# ECGCircuit.net
KiCad netlist of a schematic drawn in Altium Designer
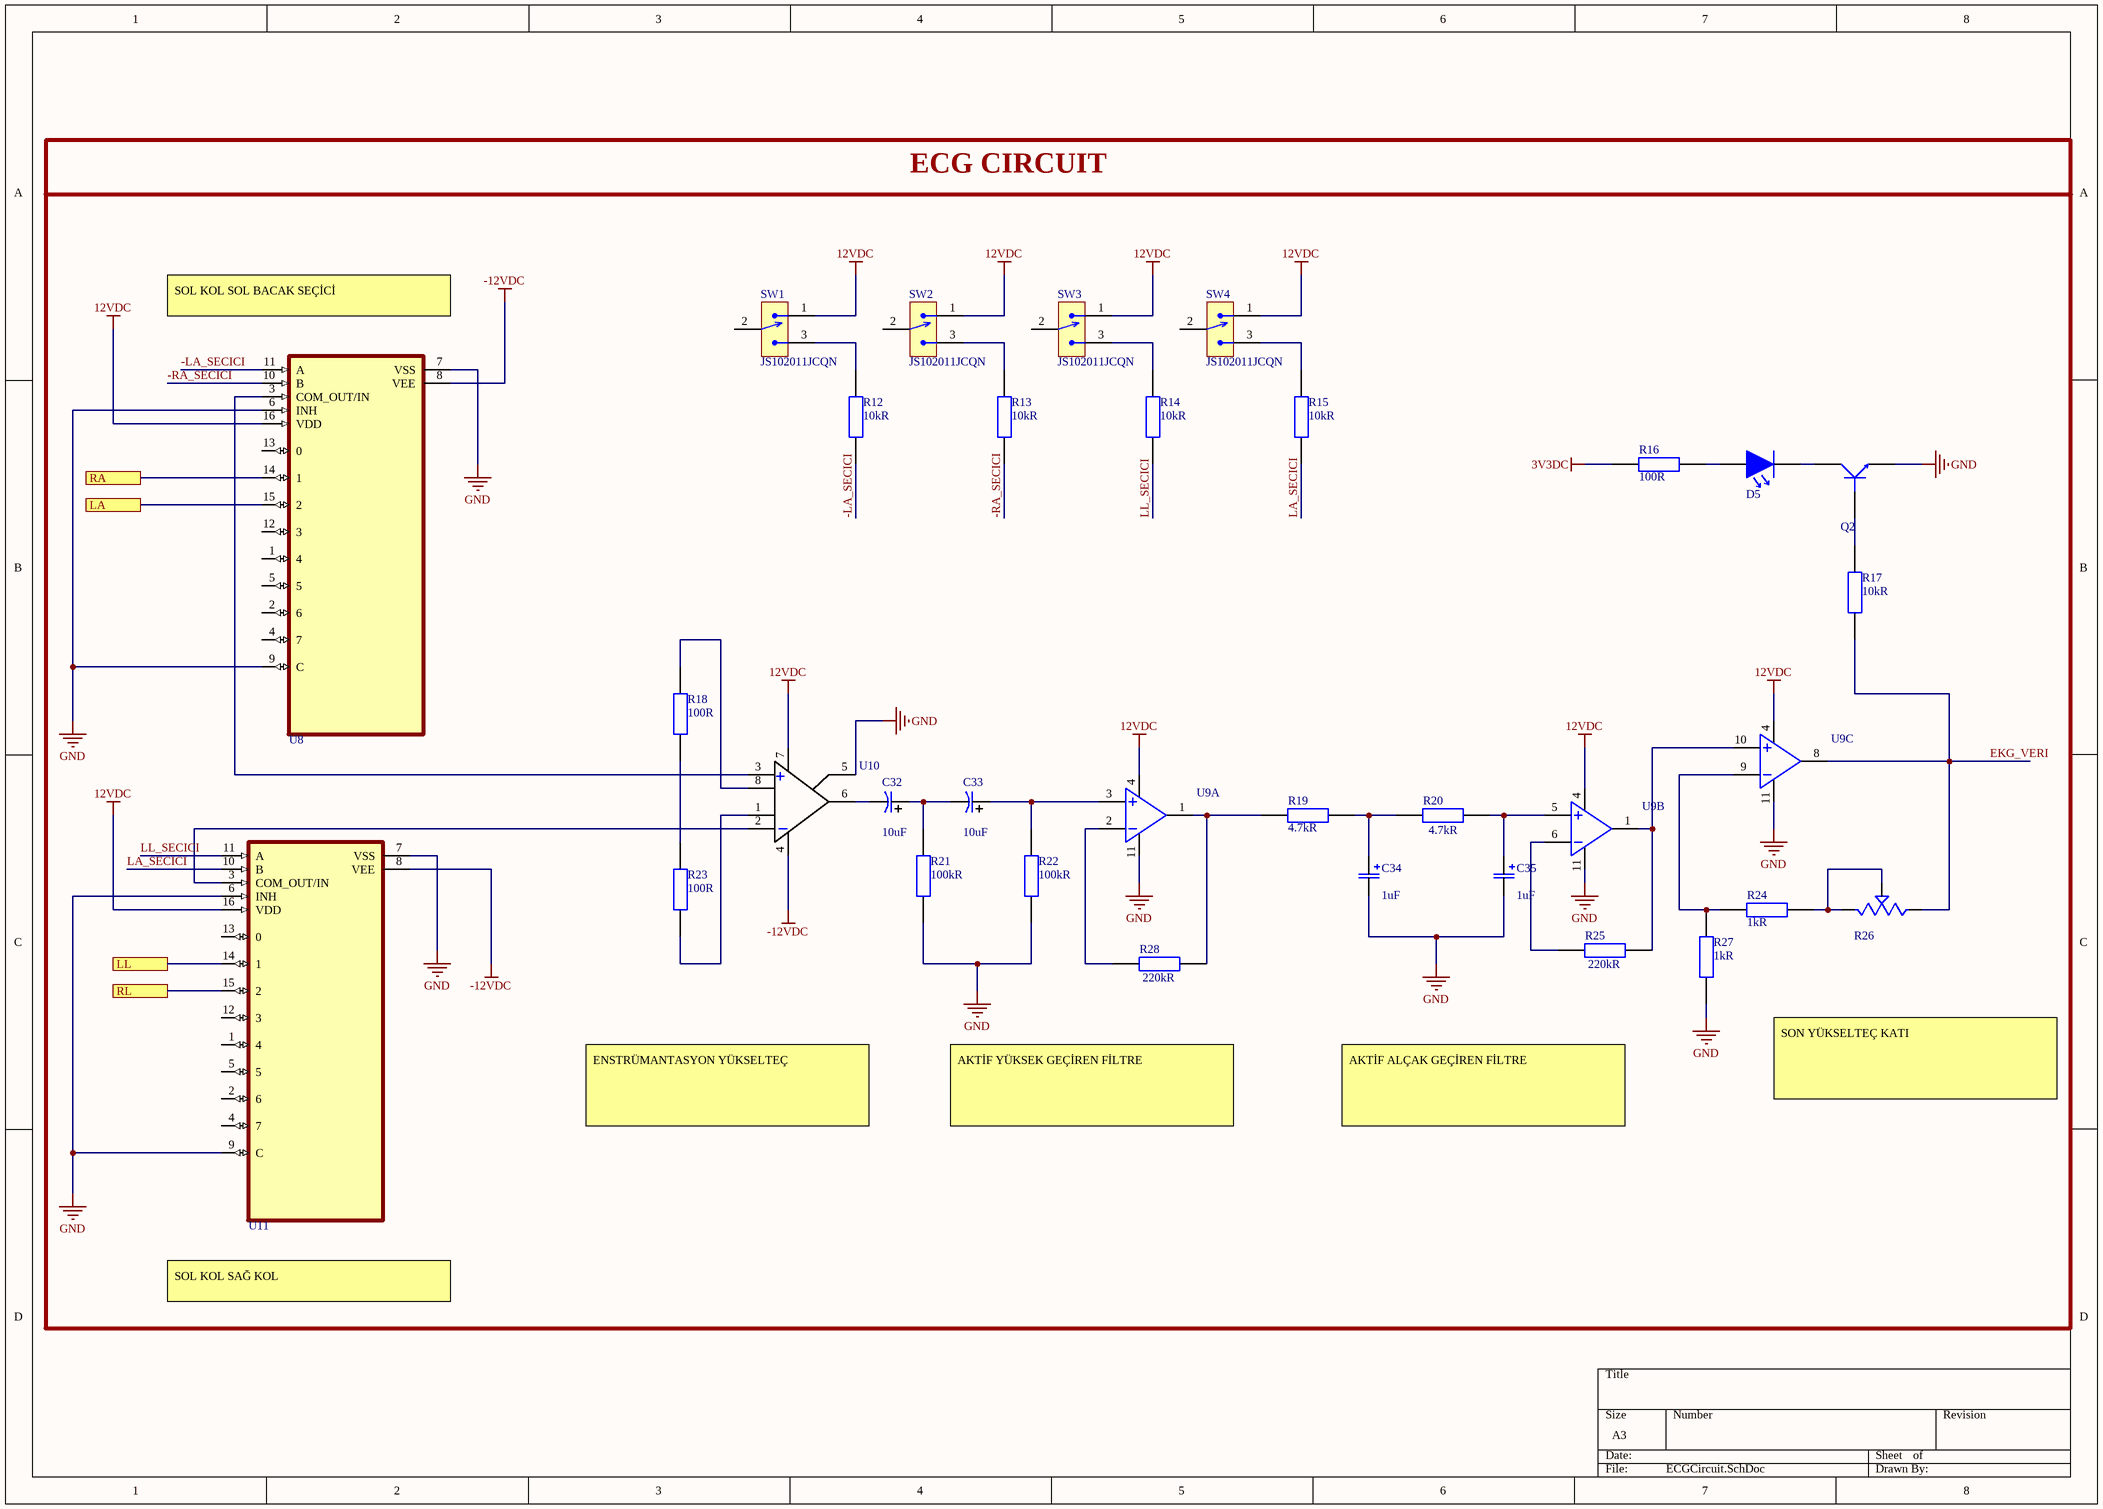
[diagram p0: ECGCircuit.SchDoc]

(export (version "E")
  (design (tool "Eeschema 10.0.6"))
  (components
    (comp (ref "C32")
      (value "AP ALU 10uF")
      (footprint "A700V_KEM")
      (description "CAP ALUM POLY 10UF 20% 12.5V SMD")
      (fields
        (field (name "MANUFACTURER") "KEMET")
        (field (name "MANUFACTURER PART NUMBER") "A700V106M12RATE040")
        (field (name "CAPACITANCE") "10uF")
      )
      (libsource (lib "Udemy_Library") (part "CAP ALU 10uF"))
    )
    (comp (ref "C33")
      (value "ALU 10uF")
      (footprint "A700V_KEM")
      (description "CAP ALUM POLY 10UF 20% 12.5V SMD")
      (fields
        (field (name "MANUFACTURER") "KEMET")
        (field (name "MANUFACTURER PART NUMBER") "A700V106M12RATE040")
        (field (name "CAPACITANCE") "10uF")
      )
      (libsource (lib "Udemy_Library") (part "CAP ALU 10uF"))
    )
    (comp (ref "C34")
      (value "CAP ALU 1uF")
      (footprint "EXV-9B_KEM")
      (description "KEMET - EXV105M050A9BAA - CAP, 1µF, 50V, RADIAL, SMD")
      (fields
        (field (name "MANUFACTURER") "KEMET")
        (field (name "MANUFACTURER PART NUMBER") "EXV105M050A9BAA")
        (field (name "CAPACITANCE") "1uF")
      )
      (libsource (lib "Udemy_Library") (part "CAP ALU 1uF"))
    )
    (comp (ref "C35")
      (value "CAP ALU 1uF")
      (footprint "EXV-9B_KEM")
      (description "KEMET - EXV105M050A9BAA - CAP, 1µF, 50V, RADIAL, SMD")
      (fields
        (field (name "MANUFACTURER") "KEMET")
        (field (name "MANUFACTURER PART NUMBER") "EXV105M050A9BAA")
        (field (name "CAPACITANCE") "1uF")
      )
      (libsource (lib "Udemy_Library") (part "CAP ALU 1uF"))
    )
    (comp (ref "D5")
      (value "LH R974-LP-1")
      (footprint "LED_RED_0805")
      (description "LED Uni-Color Hyper Red 660nm 2-Pin Chip 0805(2012Metric) T/R")
      (fields (field (name "MANUFACTURER") "Osram Opto") (field (name "DESIGNED BY") "TALAT"))
      (libsource (lib "Udemy_Library") (part "LED RED 0805"))
    )
    (comp (ref "Q2")
      (value "MMBT3904-7-F")
      (footprint "SOT-23F")
      (description "Transistor General Purpose BJT NPN 40 Volt 0.2A Automotive 3-Pin SOT-23")
      (fields (field (name "MANUFACTURER") "Diodes Zetex") (field (name "DESIGNED BY") "TALAT"))
      (libsource (lib "Udemy_Library") (part "MMBT3904-7-F"))
    )
    (comp (ref "R12")
      (value "RC0603FR-0710KL")
      (footprint "RES_0603")
      (description "RES 10K %1 OHM 0603 SMD")
      (fields
        (field (name "MANUFACTURER") "Yageo")
        (field (name "TOLERANCE") "1%")
        (field (name "RESISTANCE") "10kR")
        (field (name "DESIGNED BY") "TALAT")
      )
      (libsource (lib "Udemy_Library") (part "RES 10K OHM 0603"))
    )
    (comp (ref "R13")
      (value "RC0603FR-0710KL")
      (footprint "RES_0603")
      (description "RES 10K %1 OHM 0603 SMD")
      (fields
        (field (name "MANUFACTURER") "Yageo")
        (field (name "TOLERANCE") "1%")
        (field (name "RESISTANCE") "10kR")
        (field (name "DESIGNED BY") "TALAT")
      )
      (libsource (lib "Udemy_Library") (part "RES 10K OHM 0603"))
    )
    (comp (ref "R14")
      (value "RC0603FR-0710KL")
      (footprint "RES_0603")
      (description "RES 10K %1 OHM 0603 SMD")
      (fields
        (field (name "MANUFACTURER") "Yageo")
        (field (name "TOLERANCE") "1%")
        (field (name "RESISTANCE") "10kR")
        (field (name "DESIGNED BY") "TALAT")
      )
      (libsource (lib "Udemy_Library") (part "RES 10K OHM 0603"))
    )
    (comp (ref "R15")
      (value "RC0603FR-0710KL")
      (footprint "RES_0603")
      (description "RES 10K %1 OHM 0603 SMD")
      (fields
        (field (name "MANUFACTURER") "Yageo")
        (field (name "TOLERANCE") "1%")
        (field (name "RESISTANCE") "10kR")
        (field (name "DESIGNED BY") "TALAT")
      )
      (libsource (lib "Udemy_Library") (part "RES 10K OHM 0603"))
    )
    (comp (ref "R16")
      (value "RC0603JR-07100RL")
      (footprint "RES_0603")
      (description "RES 100 %5 OHM 0603 SMD")
      (fields
        (field (name "MANUFACTURER") "Yageo")
        (field (name "TOLERANCE") "5%")
        (field (name "RESISTANCE") "100R")
        (field (name "DESIGNED BY") "TALAT")
      )
      (libsource (lib "Udemy_Library") (part "RES 100 OHM 0603"))
    )
    (comp (ref "R17")
      (value "RC0603FR-0710KL")
      (footprint "RES_0603")
      (description "RES 10K %1 OHM 0603 SMD")
      (fields
        (field (name "MANUFACTURER") "Yageo")
        (field (name "TOLERANCE") "1%")
        (field (name "RESISTANCE") "10kR")
        (field (name "DESIGNED BY") "TALAT")
      )
      (libsource (lib "Udemy_Library") (part "RES 10K OHM 0603"))
    )
    (comp (ref "R18")
      (value "RC0603JR-07100RL")
      (footprint "RES_0603")
      (description "RES 100 %5 OHM 0603 SMD")
      (fields
        (field (name "MANUFACTURER") "Yageo")
        (field (name "TOLERANCE") "5%")
        (field (name "RESISTANCE") "100R")
        (field (name "DESIGNED BY") "TALAT")
      )
      (libsource (lib "") (part "RES 100 OHM 0603_1"))
    )
    (comp (ref "R19")
      (value "RC0603JR-074K7L")
      (footprint "RES_0603")
      (description "RES 4K7 %5 OHM 0603 SMD")
      (fields
        (field (name "MANUFACTURER") "Yageo")
        (field (name "TOLERANCE") "5%")
        (field (name "RESISTANCE") "4.7kR")
        (field (name "DESIGNED BY") "TALAT")
      )
      (libsource (lib "Udemy_Library") (part "RES 4K7 OHM 0603"))
    )
    (comp (ref "R20")
      (value "RC0603JR-074K7L")
      (footprint "RES_0603")
      (description "RES 4K7 %5 OHM 0603 SMD")
      (fields
        (field (name "MANUFACTURER") "Yageo")
        (field (name "TOLERANCE") "5%")
        (field (name "RESISTANCE") "4.7kR")
        (field (name "DESIGNED BY") "TALAT")
      )
      (libsource (lib "Udemy_Library") (part "RES 4K7 OHM 0603"))
    )
    (comp (ref "R21")
      (value "RES SMD 100KOHM 0.25% 1/10W 0603")
      (footprint "RES_0603")
      (fields
        (field (name "MANUFACTURER") "Yageo")
        (field (name "MANUFACTURER PART NUMBER") "RT0603CRE07100KL")
        (field (name "TOLERANCE") "0.25%")
        (field (name "RESISTANCE") "100kR")
      )
      (libsource (lib "Udemy_Library") (part "RES 100K OHM 0603"))
    )
    (comp (ref "R22")
      (value "RES SMD 100KOHM 0.25% 1/10W 0603")
      (footprint "RES_0603")
      (fields
        (field (name "MANUFACTURER") "Yageo")
        (field (name "MANUFACTURER PART NUMBER") "RT0603CRE07100KL")
        (field (name "TOLERANCE") "0.25%")
        (field (name "RESISTANCE") "100kR")
      )
      (libsource (lib "Udemy_Library") (part "RES 100K OHM 0603"))
    )
    (comp (ref "R23")
      (value "RC0603JR-07100RL")
      (footprint "RES_0603")
      (description "RES 100 %5 OHM 0603 SMD")
      (fields
        (field (name "MANUFACTURER") "Yageo")
        (field (name "TOLERANCE") "5%")
        (field (name "RESISTANCE") "100R")
        (field (name "DESIGNED BY") "TALAT")
      )
      (libsource (lib "") (part "RES 100 OHM 0603_1"))
    )
    (comp (ref "R24")
      (value "RC0603FR-0710KL")
      (footprint "RES_0603")
      (description "RES 1K %1 OHM 0603 SMD")
      (fields
        (field (name "MANUFACTURER") "Yageo")
        (field (name "MANUFACTURER PART NUMBER") "RC0603JR-071KL")
        (field (name "RESISTANCE") "1kR")
        (field (name "DESIGNED BY") "TALAT")
      )
      (libsource (lib "") (part "RES 1K OHM 0603_1"))
    )
    (comp (ref "R25")
      (value "RC0603JR-07220KL")
      (footprint "RES_0603")
      (description "RES 220K %5 OHM 0603 SMD")
      (fields
        (field (name "MANUFACTURER") "Yageo")
        (field (name "TOLERANCE") "5%")
        (field (name "RESISTANCE") "220kR")
      )
      (libsource (lib "Udemy_Library") (part "RES 220K OHM 0603"))
    )
    (comp (ref "R26")
      (value "TRIMMER, 12 TURN 50K")
      (footprint "3266W-1-503LF")
      (fields
        (field (name "MANUFACTURER") "Bourns")
        (field (name "MANUFACTURER PART NUMBER") "3266W-1-503LF")
        (field (name "TOLERANCE") "10%")
        (field (name "DESIGNED BY") "TALAT")
      )
      (libsource (lib "Udemy_Library") (part "Res POT 50K"))
    )
    (comp (ref "R27")
      (value "RC0603FR-0710KL")
      (footprint "RES_0603")
      (description "RES 1K %1 OHM 0603 SMD")
      (fields
        (field (name "MANUFACTURER") "Yageo")
        (field (name "MANUFACTURER PART NUMBER") "RC0603JR-071KL")
        (field (name "RESISTANCE") "1kR")
        (field (name "DESIGNED BY") "TALAT")
      )
      (libsource (lib "Udemy_Library") (part "RES 1K OHM 0603"))
    )
    (comp (ref "R28")
      (value "RC0603JR-07220KL")
      (footprint "RES_0603")
      (description "RES 220K %5 OHM 0603 SMD")
      (fields
        (field (name "MANUFACTURER") "Yageo")
        (field (name "TOLERANCE") "5%")
        (field (name "RESISTANCE") "220kR")
      )
      (libsource (lib "Udemy_Library") (part "RES 220K OHM 0603"))
    )
    (comp (ref "SW1")
      (value "JS102011JCQN")
      (footprint "JS102011JCQN")
      (libsource (lib "Udemy_Library") (part "JS102011JCQN"))
    )
    (comp (ref "SW2")
      (value "JS102011JCQN")
      (footprint "JS102011JCQN")
      (libsource (lib "Udemy_Library") (part "JS102011JCQN"))
    )
    (comp (ref "SW3")
      (value "JS102011JCQN")
      (footprint "JS102011JCQN")
      (libsource (lib "Udemy_Library") (part "JS102011JCQN"))
    )
    (comp (ref "SW4")
      (value "JS102011JCQN")
      (footprint "JS102011JCQN")
      (libsource (lib "Udemy_Library") (part "JS102011JCQN"))
    )
    (comp (ref "U8")
      (value "CD4051BM")
      (footprint "SOİC16")
      (description "Analog Multiplexer Single 8:1 16-Pin SOIC Tube")
      (fields (field (name "MANUFACTURER") "Texas Instruments"))
      (libsource (lib "Udemy_Library") (part "CD4051BM"))
    )
    (comp (ref "U9")
      (value "IC OPAMP GP 1.3MHZ 14DIP")
      (footprint "SOIC14")
      (fields
        (field (name "MANUFACTURER") "STMicroelectronics")
        (field (name "MANUFACTURER PART NUMBER") "LM324N")
        (field (name "DESIGNED BY") "Talat")
      )
      (libsource (lib "Udemy_Library") (part "OPALM324N"))
    )
    (comp (ref "U10")
      (value "AD620BRZ-R7")
      (footprint "SOIC8")
      (description "SP Amp INSTR Amp Single ±18V 8-Pin SOIC N T/R")
      (fields (field (name "MANUFACTURER") "Analog Devices"))
      (libsource (lib "Udemy_Library") (part "AD620"))
    )
    (comp (ref "U11")
      (value "CD4051BM")
      (footprint "SOİC16")
      (description "Analog Multiplexer Single 8:1 16-Pin SOIC Tube")
      (fields (field (name "MANUFACTURER") "Texas Instruments"))
      (libsource (lib "Udemy_Library") (part "CD4051BM"))
    )
  )
  (nets
    (net (code "1") (name "-12VDC") (class "Default")
      (node (ref "U10") (pin "4") (pinfunction "4_4") (pintype "passive"))
      (node (ref "U11") (pin "8") (pinfunction "VEE_8") (pintype "power_in"))
      (node (ref "U8") (pin "8") (pinfunction "VEE_8") (pintype "power_in"))
    )
    (net (code "2") (name "/-LA_SECICI") (class "Default")
      (node (ref "R12") (pin "1") (pinfunction "1_1") (pintype "passive"))
      (node (ref "U8") (pin "11") (pinfunction "A_11") (pintype "input"))
    )
    (net (code "3") (name "/-RA_SECICI") (class "Default")
      (node (ref "R13") (pin "1") (pinfunction "1_1") (pintype "passive"))
      (node (ref "U8") (pin "10") (pinfunction "B_10") (pintype "input"))
    )
    (net (code "4") (name "/EKG_VERI") (class "Default")
      (node (ref "R17") (pin "1") (pinfunction "1_1") (pintype "passive"))
      (node (ref "R26") (pin "1") (pinfunction "CCW_1") (pintype "passive"))
      (node (ref "U9") (pin "8") (pinfunction "8_8") (pintype "passive"))
    )
    (net (code "5") (name "/LA") (class "Default")
      (node (ref "U8") (pin "15") (pinfunction "2_15") (pintype "bidirectional"))
    )
    (net (code "6") (name "/LA_SECICI") (class "Default")
      (node (ref "R15") (pin "1") (pinfunction "1_1") (pintype "passive"))
      (node (ref "U11") (pin "10") (pinfunction "B_10") (pintype "input"))
    )
    (net (code "7") (name "/LL") (class "Default")
      (node (ref "U11") (pin "14") (pinfunction "1_14") (pintype "bidirectional"))
    )
    (net (code "8") (name "/LL_SECICI") (class "Default")
      (node (ref "R14") (pin "1") (pinfunction "1_1") (pintype "passive"))
      (node (ref "U11") (pin "11") (pinfunction "A_11") (pintype "input"))
    )
    (net (code "9") (name "/RA") (class "Default")
      (node (ref "U8") (pin "14") (pinfunction "1_14") (pintype "bidirectional"))
    )
    (net (code "10") (name "/RL") (class "Default")
      (node (ref "U11") (pin "15") (pinfunction "2_15") (pintype "bidirectional"))
    )
    (net (code "11") (name "3V3DC") (class "Default")
      (node (ref "R16") (pin "2") (pinfunction "2_2") (pintype "passive"))
    )
    (net (code "12") (name "12VDC") (class "Default")
      (node (ref "SW1") (pin "1") (pinfunction "1_1") (pintype "passive"))
      (node (ref "SW2") (pin "1") (pinfunction "1_1") (pintype "passive"))
      (node (ref "SW3") (pin "1") (pinfunction "1_1") (pintype "passive"))
      (node (ref "SW4") (pin "1") (pinfunction "1_1") (pintype "passive"))
      (node (ref "U10") (pin "7") (pinfunction "7_7") (pintype "passive"))
      (node (ref "U11") (pin "16") (pinfunction "VDD_16") (pintype "input"))
      (node (ref "U8") (pin "16") (pinfunction "VDD_16") (pintype "input"))
      (node (ref "U9") (pin "4") (pinfunction "4_4") (pintype "passive"))
    )
    (net (code "13") (name "GND") (class "Default")
      (node (ref "C34") (pin "2") (pinfunction "12_2") (pintype "passive"))
      (node (ref "C35") (pin "2") (pinfunction "12_2") (pintype "passive"))
      (node (ref "Q2") (pin "2") (pinfunction "E_2") (pintype "power_in"))
      (node (ref "R21") (pin "1") (pinfunction "1_1") (pintype "passive"))
      (node (ref "R22") (pin "1") (pinfunction "1_1") (pintype "passive"))
      (node (ref "R27") (pin "1") (pinfunction "1_1") (pintype "passive"))
      (node (ref "U10") (pin "5") (pinfunction "5_5") (pintype "passive"))
      (node (ref "U11") (pin "6") (pinfunction "INH_6") (pintype "input"))
      (node (ref "U11") (pin "7") (pinfunction "VSS_7") (pintype "power_in"))
      (node (ref "U11") (pin "9") (pinfunction "C_9") (pintype "bidirectional"))
      (node (ref "U8") (pin "6") (pinfunction "INH_6") (pintype "input"))
      (node (ref "U8") (pin "7") (pinfunction "VSS_7") (pintype "power_in"))
      (node (ref "U8") (pin "9") (pinfunction "C_9") (pintype "bidirectional"))
      (node (ref "U9") (pin "11") (pinfunction "11_11") (pintype "passive"))
    )
    (net (code "14") (name "Net-(C32-Pad1)") (class "Default")
      (node (ref "C32") (pin "1") (pinfunction "1_1") (pintype "passive"))
      (node (ref "C33") (pin "2") (pinfunction "2_2") (pintype "passive"))
      (node (ref "R21") (pin "2") (pinfunction "2_2") (pintype "passive"))
    )
    (net (code "15") (name "Net-(C32-Pad2)") (class "Default")
      (node (ref "C32") (pin "2") (pinfunction "2_2") (pintype "passive"))
      (node (ref "U10") (pin "6") (pinfunction "6_6") (pintype "passive"))
    )
    (net (code "16") (name "Net-(C33-Pad1)") (class "Default")
      (node (ref "C33") (pin "1") (pinfunction "1_1") (pintype "passive"))
      (node (ref "R22") (pin "2") (pinfunction "2_2") (pintype "passive"))
      (node (ref "U9") (pin "3") (pinfunction "3_3") (pintype "passive"))
    )
    (net (code "17") (name "Net-(C34-11)") (class "Default")
      (node (ref "C34") (pin "1") (pinfunction "11_1") (pintype "passive"))
      (node (ref "R19") (pin "2") (pinfunction "2_2") (pintype "passive"))
      (node (ref "R20") (pin "1") (pinfunction "1_1") (pintype "passive"))
    )
    (net (code "18") (name "Net-(C35-11)") (class "Default")
      (node (ref "C35") (pin "1") (pinfunction "11_1") (pintype "passive"))
      (node (ref "R20") (pin "2") (pinfunction "2_2") (pintype "passive"))
      (node (ref "U9") (pin "5") (pinfunction "5_5") (pintype "passive"))
    )
    (net (code "19") (name "Net-(D5-Pad2)") (class "Default")
      (node (ref "D5") (pin "2") (pinfunction "2_2") (pintype "power_in"))
      (node (ref "R16") (pin "1") (pinfunction "1_1") (pintype "passive"))
    )
    (net (code "20") (name "Net-(Q2-B)") (class "Default")
      (node (ref "Q2") (pin "1") (pinfunction "B_1") (pintype "power_in"))
      (node (ref "R17") (pin "2") (pinfunction "2_2") (pintype "passive"))
    )
    (net (code "21") (name "Net-(Q2-C)") (class "Default")
      (node (ref "D5") (pin "1") (pinfunction "1_1") (pintype "power_in"))
      (node (ref "Q2") (pin "3") (pinfunction "C_3") (pintype "power_in"))
    )
    (net (code "22") (name "Net-(R12-Pad2)") (class "Default")
      (node (ref "R12") (pin "2") (pinfunction "2_2") (pintype "passive"))
      (node (ref "SW1") (pin "3") (pinfunction "3_3") (pintype "passive"))
    )
    (net (code "23") (name "Net-(R13-Pad2)") (class "Default")
      (node (ref "R13") (pin "2") (pinfunction "2_2") (pintype "passive"))
      (node (ref "SW2") (pin "3") (pinfunction "3_3") (pintype "passive"))
    )
    (net (code "24") (name "Net-(R14-Pad2)") (class "Default")
      (node (ref "R14") (pin "2") (pinfunction "2_2") (pintype "passive"))
      (node (ref "SW3") (pin "3") (pinfunction "3_3") (pintype "passive"))
    )
    (net (code "25") (name "Net-(R15-Pad2)") (class "Default")
      (node (ref "R15") (pin "2") (pinfunction "2_2") (pintype "passive"))
      (node (ref "SW4") (pin "3") (pinfunction "3_3") (pintype "passive"))
    )
    (net (code "26") (name "Net-(R18-Pad1)") (class "Default")
      (node (ref "R18") (pin "1") (pinfunction "1_1") (pintype "passive"))
      (node (ref "R23") (pin "2") (pinfunction "2_2") (pintype "passive"))
    )
    (net (code "27") (name "Net-(R18-Pad2)") (class "Default")
      (node (ref "R18") (pin "2") (pinfunction "2_2") (pintype "passive"))
      (node (ref "U10") (pin "8") (pinfunction "8_8") (pintype "passive"))
    )
    (net (code "28") (name "Net-(R19-Pad1)") (class "Default")
      (node (ref "R19") (pin "1") (pinfunction "1_1") (pintype "passive"))
      (node (ref "R28") (pin "2") (pinfunction "2_2") (pintype "passive"))
      (node (ref "U9") (pin "1") (pinfunction "1_1") (pintype "passive"))
    )
    (net (code "29") (name "Net-(R23-Pad1)") (class "Default")
      (node (ref "R23") (pin "1") (pinfunction "1_1") (pintype "passive"))
      (node (ref "U10") (pin "1") (pinfunction "1_1") (pintype "passive"))
    )
    (net (code "30") (name "Net-(R24-Pad1)") (class "Default")
      (node (ref "R24") (pin "1") (pinfunction "1_1") (pintype "passive"))
      (node (ref "R27") (pin "2") (pinfunction "2_2") (pintype "passive"))
      (node (ref "U9") (pin "9") (pinfunction "9_9") (pintype "passive"))
    )
    (net (code "31") (name "Net-(R25-Pad1)") (class "Default")
      (node (ref "R25") (pin "1") (pinfunction "1_1") (pintype "passive"))
      (node (ref "U9") (pin "6") (pinfunction "6_6") (pintype "passive"))
    )
    (net (code "32") (name "Net-(R26-CW)") (class "Default")
      (node (ref "R24") (pin "2") (pinfunction "2_2") (pintype "passive"))
      (node (ref "R26") (pin "2") (pinfunction "WIPER_2") (pintype "passive"))
      (node (ref "R26") (pin "3") (pinfunction "CW_3") (pintype "passive"))
    )
    (net (code "33") (name "Net-(R28-Pad1)") (class "Default")
      (node (ref "R28") (pin "1") (pinfunction "1_1") (pintype "passive"))
      (node (ref "U9") (pin "2") (pinfunction "2_2") (pintype "passive"))
    )
    (net (code "34") (name "Net-(U8-COM_OUT{slash}IN)") (class "Default")
      (node (ref "U10") (pin "3") (pinfunction "3_3") (pintype "passive"))
      (node (ref "U8") (pin "3") (pinfunction "COM_OUT/IN_3") (pintype "input"))
    )
    (net (code "35") (name "Net-(U9B-7)") (class "Default")
      (node (ref "R25") (pin "2") (pinfunction "2_2") (pintype "passive"))
      (node (ref "U9") (pin "1") (pinfunction "7_1") (pintype "passive"))
      (node (ref "U9") (pin "10") (pinfunction "10_10") (pintype "passive"))
    )
    (net (code "36") (name "Net-(U11-COM_OUT{slash}IN)") (class "Default")
      (node (ref "U10") (pin "2") (pinfunction "2_2") (pintype "passive"))
      (node (ref "U11") (pin "3") (pinfunction "COM_OUT/IN_3") (pintype "input"))
    )
    (net (code "37") (name "unconnected-(SW1-Pad2)") (class "Default")
      (node (ref "SW1") (pin "2") (pinfunction "2_2") (pintype "passive"))
    )
    (net (code "38") (name "unconnected-(SW2-Pad2)") (class "Default")
      (node (ref "SW2") (pin "2") (pinfunction "2_2") (pintype "passive"))
    )
    (net (code "39") (name "unconnected-(SW3-Pad2)") (class "Default")
      (node (ref "SW3") (pin "2") (pinfunction "2_2") (pintype "passive"))
    )
    (net (code "40") (name "unconnected-(SW4-Pad2)") (class "Default")
      (node (ref "SW4") (pin "2") (pinfunction "2_2") (pintype "passive"))
    )
    (net (code "41") (name "unconnected-(U8-0-Pad13)") (class "Default")
      (node (ref "U8") (pin "13") (pinfunction "0_13") (pintype "bidirectional"))
    )
    (net (code "42") (name "unconnected-(U8-3-Pad12)") (class "Default")
      (node (ref "U8") (pin "12") (pinfunction "3_12") (pintype "bidirectional"))
    )
    (net (code "43") (name "unconnected-(U8-4-Pad1)") (class "Default")
      (node (ref "U8") (pin "1") (pinfunction "4_1") (pintype "bidirectional"))
    )
    (net (code "44") (name "unconnected-(U8-6-Pad2)") (class "Default")
      (node (ref "U8") (pin "2") (pinfunction "6_2") (pintype "bidirectional"))
    )
    (net (code "45") (name "unconnected-(U8-7-Pad4)") (class "Default")
      (node (ref "U8") (pin "4") (pinfunction "7_4") (pintype "bidirectional"))
    )
    (net (code "46") (name "unconnected-(U8-Pad5)") (class "Default")
      (node (ref "U8") (pin "5") (pinfunction "5_5") (pintype "bidirectional"))
    )
    (net (code "47") (name "unconnected-(U11-0-Pad13)") (class "Default")
      (node (ref "U11") (pin "13") (pinfunction "0_13") (pintype "bidirectional"))
    )
    (net (code "48") (name "unconnected-(U11-3-Pad12)") (class "Default")
      (node (ref "U11") (pin "12") (pinfunction "3_12") (pintype "bidirectional"))
    )
    (net (code "49") (name "unconnected-(U11-4-Pad1)") (class "Default")
      (node (ref "U11") (pin "1") (pinfunction "4_1") (pintype "bidirectional"))
    )
    (net (code "50") (name "unconnected-(U11-6-Pad2)") (class "Default")
      (node (ref "U11") (pin "2") (pinfunction "6_2") (pintype "bidirectional"))
    )
    (net (code "51") (name "unconnected-(U11-7-Pad4)") (class "Default")
      (node (ref "U11") (pin "4") (pinfunction "7_4") (pintype "bidirectional"))
    )
    (net (code "52") (name "unconnected-(U11-Pad5)") (class "Default")
      (node (ref "U11") (pin "5") (pinfunction "5_5") (pintype "bidirectional"))
    )
  )
)
